# Filamint_Schematic_V4_3.net
KiCad netlist of a schematic drawn in EAGLE
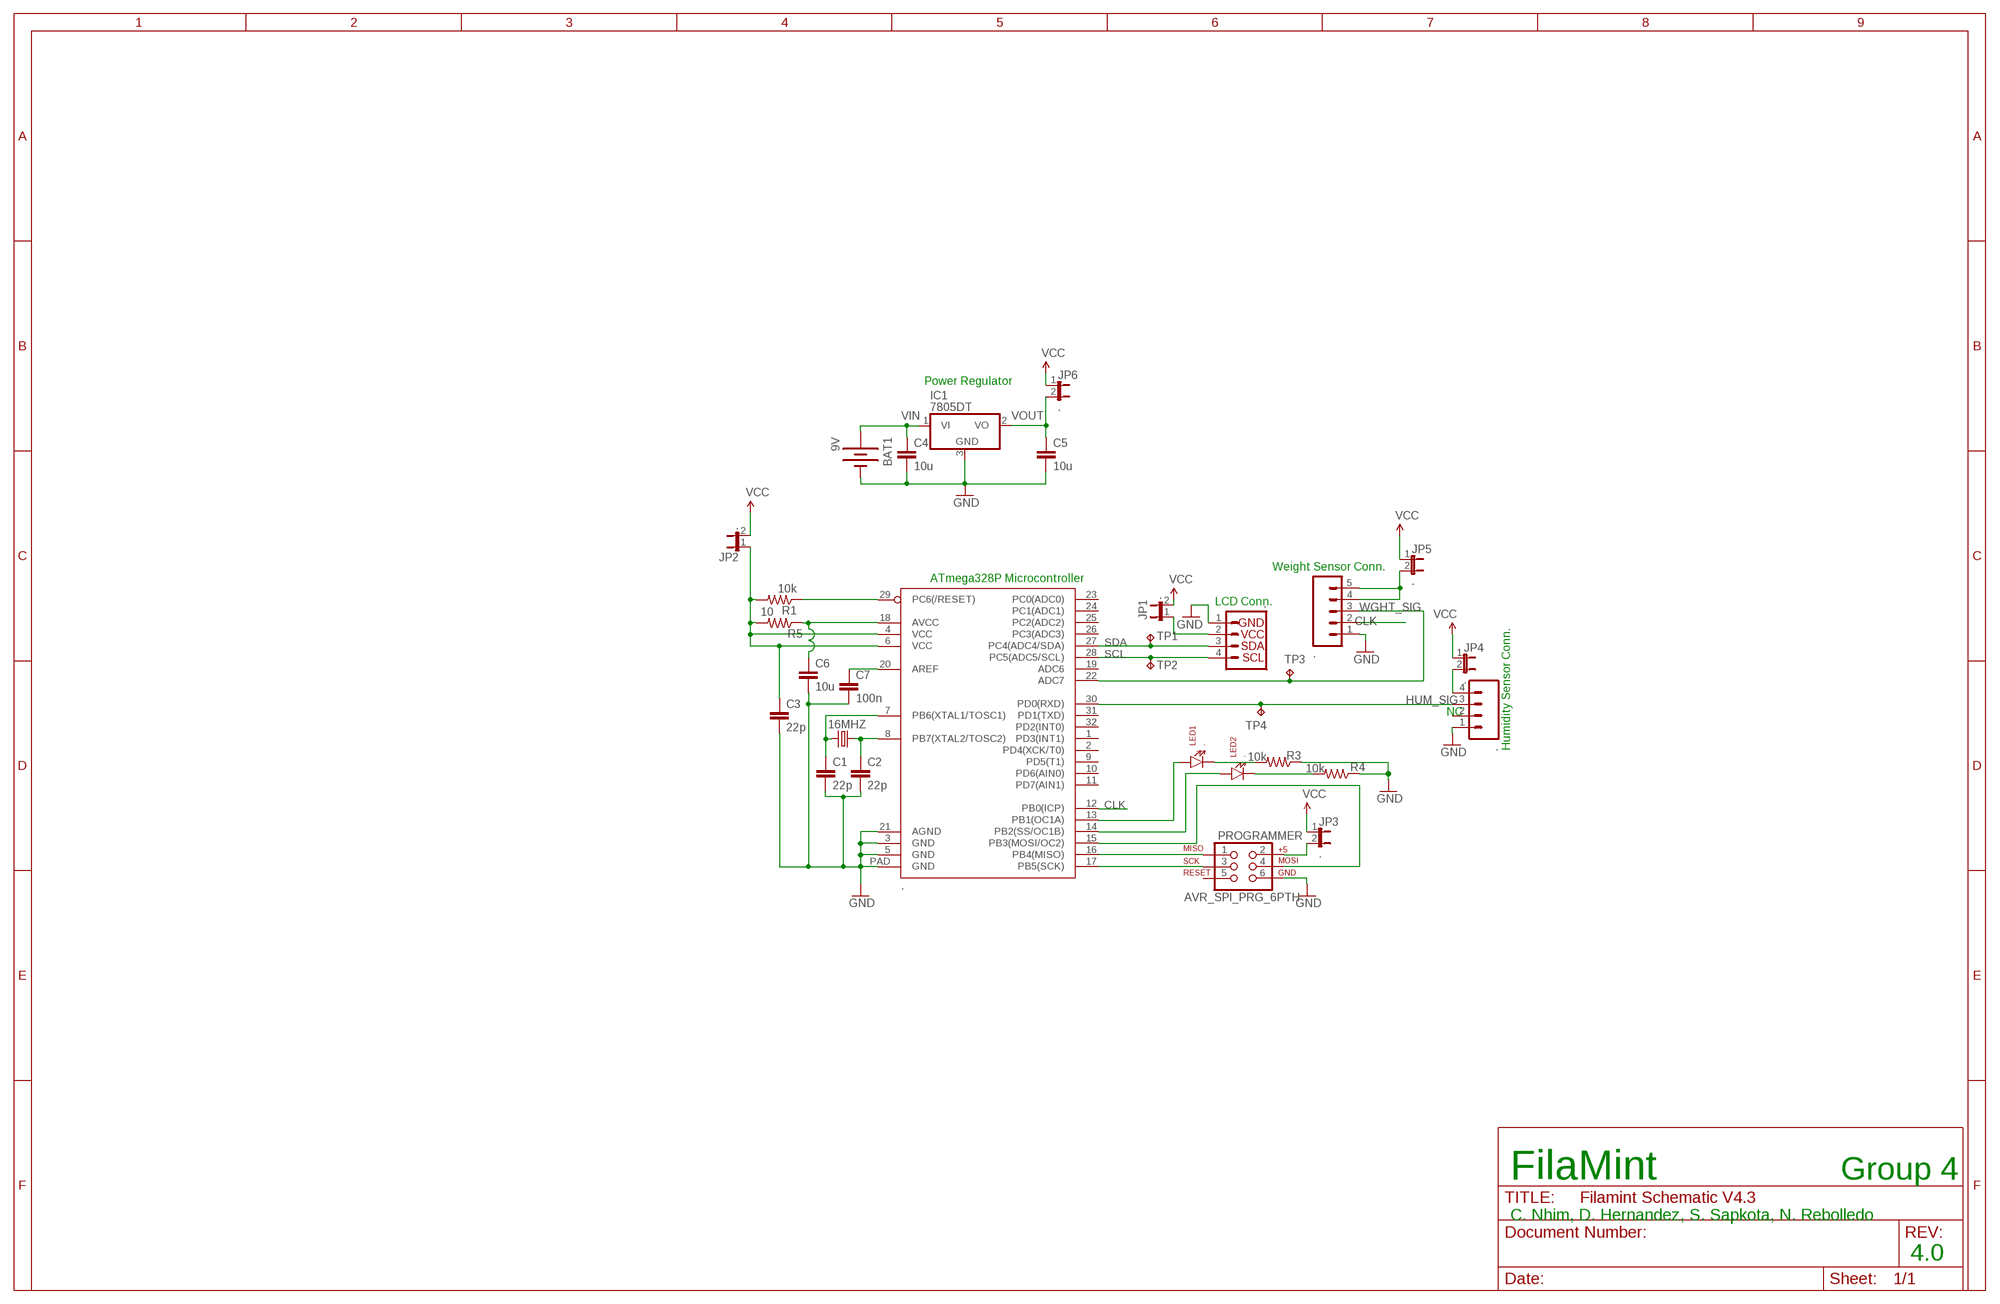
[diagram p0: schematic, sheet 1]

(export (version "E")
  (design (tool "Eeschema 10.0.6"))
  (components
    (comp (ref "16MHZ")
      (value "CSM-7X-DU")
      (footprint "eagle-import:CSM-7X-DU")
      (libsource (lib "eagle-import") (part "CSM-7X-DU"))
    )
    (comp (ref "BAT1")
      (value "9V")
      (footprint "eagle-import:BATTCON_9V")
      (libsource (lib "eagle-import") (part "BATTERY9V"))
    )
    (comp (ref "C1")
      (value "22p")
      (footprint "eagle-import:C025-024X044")
      (libsource (lib "eagle-import") (part "C-EU025-024X044"))
    )
    (comp (ref "C2")
      (value "22p")
      (footprint "eagle-import:C025-024X044")
      (libsource (lib "eagle-import") (part "C-EU025-024X044"))
    )
    (comp (ref "C3")
      (value "22p")
      (footprint "eagle-import:C025-024X044")
      (libsource (lib "eagle-import") (part "C-EU025-024X044"))
    )
    (comp (ref "C4")
      (value "10u")
      (footprint "eagle-import:C025-024X044")
      (libsource (lib "eagle-import") (part "C-EU025-024X044"))
    )
    (comp (ref "C5")
      (value "10u")
      (footprint "eagle-import:C025-024X044")
      (libsource (lib "eagle-import") (part "C-EU025-024X044"))
    )
    (comp (ref "C6")
      (value "10u")
      (footprint "eagle-import:C025-024X044")
      (libsource (lib "eagle-import") (part "C-EU025-024X044"))
    )
    (comp (ref "C7")
      (value "100n")
      (footprint "eagle-import:C025-024X044")
      (libsource (lib "eagle-import") (part "C-EU025-024X044"))
    )
    (comp (ref "DHT22")
      (value ".")
      (footprint "eagle-import:1X04-1MM-RA")
      (libsource (lib "eagle-import") (part "M04SMD2"))
    )
    (comp (ref "HX711")
      (value ".")
      (footprint "eagle-import:1X05-1MM")
      (libsource (lib "eagle-import") (part "M05SMD"))
    )
    (comp (ref "IC1")
      (value "7805DT")
      (footprint "eagle-import:TO252")
      (libsource (lib "eagle-import") (part "78DT05"))
    )
    (comp (ref "JP1")
      (value ".")
      (footprint "eagle-import:JP1")
      (libsource (lib "eagle-import") (part "JP1E"))
    )
    (comp (ref "JP2")
      (value ".")
      (footprint "eagle-import:JP1")
      (libsource (lib "eagle-import") (part "JP1E"))
    )
    (comp (ref "JP3")
      (value ".")
      (footprint "eagle-import:JP1")
      (libsource (lib "eagle-import") (part "JP1E"))
    )
    (comp (ref "JP4")
      (value ".")
      (footprint "eagle-import:JP1")
      (libsource (lib "eagle-import") (part "JP1E"))
    )
    (comp (ref "JP5")
      (value ".")
      (footprint "eagle-import:JP1")
      (libsource (lib "eagle-import") (part "JP1E"))
    )
    (comp (ref "JP6")
      (value ".")
      (footprint "eagle-import:JP1")
      (libsource (lib "eagle-import") (part "JP1E"))
    )
    (comp (ref "LCD")
      (value ".")
      (footprint "eagle-import:1X04")
      (libsource (lib "eagle-import") (part "I2C_STANDARD"))
    )
    (comp (ref "LED1")
      (value ".")
      (footprint "eagle-import:LTE-302")
      (libsource (lib "eagle-import") (part "LTE-302"))
    )
    (comp (ref "LED2")
      (value ".")
      (footprint "eagle-import:LTE-302")
      (libsource (lib "eagle-import") (part "LTE-302"))
    )
    (comp (ref "MICROCONTROLLER")
      (value ".")
      (footprint "eagle-import:MLF32-PAD")
      (libsource (lib "eagle-import") (part "ATMEGA328P_MLFMLF32"))
    )
    (comp (ref "PROGRAMMER")
      (value "AVR_SPI_PRG_6PTH")
      (footprint "eagle-import:2X3")
      (libsource (lib "eagle-import") (part "AVR_SPI_PRG_6PTH"))
    )
    (comp (ref "R1")
      (value "10k")
      (footprint "eagle-import:0204_5")
      (libsource (lib "eagle-import") (part "R-US_0204/5"))
    )
    (comp (ref "R3")
      (value "10k")
      (footprint "eagle-import:0204_5")
      (libsource (lib "eagle-import") (part "R-US_0204/5"))
    )
    (comp (ref "R4")
      (value "10k")
      (footprint "eagle-import:0204_5")
      (libsource (lib "eagle-import") (part "R-US_0204/5"))
    )
    (comp (ref "R5")
      (value "10")
      (footprint "eagle-import:0204_5")
      (libsource (lib "eagle-import") (part "R-US_0204/5"))
    )
    (comp (ref "TP1")
      (value "TPB1,27")
      (footprint "eagle-import:B1,27")
      (libsource (lib "eagle-import") (part "TPB1,27"))
    )
    (comp (ref "TP2")
      (value "TPB1,27")
      (footprint "eagle-import:B1,27")
      (libsource (lib "eagle-import") (part "TPB1,27"))
    )
    (comp (ref "TP3")
      (value "TPB1,27")
      (footprint "eagle-import:B1,27")
      (libsource (lib "eagle-import") (part "TPB1,27"))
    )
    (comp (ref "TP4")
      (value "TPB1,27")
      (footprint "eagle-import:B1,27")
      (libsource (lib "eagle-import") (part "TPB1,27"))
    )
  )
  (nets
    (net (code "1") (name "/CLK") (class "Default")
      (node (ref "HX711") (pin "2") (pinfunction "2_2") (pintype "passive"))
      (node (ref "MICROCONTROLLER") (pin "12") (pinfunction "PB0(ICP)_12") (pintype "bidirectional"))
    )
    (net (code "2") (name "/HUM_SIG") (class "Default")
      (node (ref "DHT22") (pin "3") (pinfunction "3_3") (pintype "passive"))
      (node (ref "MICROCONTROLLER") (pin "30") (pinfunction "PD0(RXD)_30") (pintype "bidirectional"))
      (node (ref "TP4") (pin "TP") (pinfunction "TP_TP") (pintype "input"))
    )
    (net (code "3") (name "/SCL") (class "Default")
      (node (ref "LCD") (pin "4") (pinfunction "4_4") (pintype "passive"))
      (node (ref "MICROCONTROLLER") (pin "28") (pinfunction "PC5(ADC5/SCL)_28") (pintype "bidirectional"))
      (node (ref "TP2") (pin "TP") (pinfunction "TP_TP") (pintype "input"))
    )
    (net (code "4") (name "/SDA") (class "Default")
      (node (ref "LCD") (pin "3") (pinfunction "3_3") (pintype "passive"))
      (node (ref "MICROCONTROLLER") (pin "27") (pinfunction "PC4(ADC4/SDA)_27") (pintype "bidirectional"))
      (node (ref "TP1") (pin "TP") (pinfunction "TP_TP") (pintype "input"))
    )
    (net (code "5") (name "/VIN") (class "Default")
      (node (ref "BAT1") (pin "+") (pinfunction "+_+") (pintype "power_in"))
      (node (ref "C4") (pin "1") (pinfunction "1_1") (pintype "passive"))
      (node (ref "IC1") (pin "1") (pinfunction "VI_1") (pintype "input"))
    )
    (net (code "6") (name "/WGHT_SIG") (class "Default")
      (node (ref "HX711") (pin "3") (pinfunction "3_3") (pintype "passive"))
      (node (ref "MICROCONTROLLER") (pin "22") (pinfunction "ADC7_22") (pintype "bidirectional"))
      (node (ref "TP3") (pin "TP") (pinfunction "TP_TP") (pintype "input"))
    )
    (net (code "7") (name "GND") (class "Default")
      (node (ref "BAT1") (pin "-") (pinfunction "-_-") (pintype "power_in"))
      (node (ref "C1") (pin "2") (pinfunction "2_2") (pintype "passive"))
      (node (ref "C2") (pin "2") (pinfunction "2_2") (pintype "passive"))
      (node (ref "C3") (pin "2") (pinfunction "2_2") (pintype "passive"))
      (node (ref "C4") (pin "2") (pinfunction "2_2") (pintype "passive"))
      (node (ref "C5") (pin "2") (pinfunction "2_2") (pintype "passive"))
      (node (ref "C6") (pin "2") (pinfunction "2_2") (pintype "passive"))
      (node (ref "C7") (pin "2") (pinfunction "2_2") (pintype "passive"))
      (node (ref "DHT22") (pin "1") (pinfunction "1_1") (pintype "passive"))
      (node (ref "HX711") (pin "1") (pinfunction "1_1") (pintype "passive"))
      (node (ref "IC1") (pin "3") (pinfunction "GND_3") (pintype "passive"))
      (node (ref "LCD") (pin "1") (pinfunction "1_1") (pintype "passive"))
      (node (ref "MICROCONTROLLER") (pin "21") (pinfunction "AGND_21") (pintype "bidirectional"))
      (node (ref "MICROCONTROLLER") (pin "3") (pinfunction "GND_3") (pintype "bidirectional"))
      (node (ref "MICROCONTROLLER") (pin "5") (pinfunction "GND_5") (pintype "bidirectional"))
      (node (ref "MICROCONTROLLER") (pin "PAD") (pinfunction "GND_PAD") (pintype "bidirectional"))
      (node (ref "PROGRAMMER") (pin "6") (pinfunction "6_6") (pintype "passive"))
      (node (ref "R3") (pin "1") (pinfunction "1_1") (pintype "passive"))
      (node (ref "R4") (pin "1") (pinfunction "1_1") (pintype "passive"))
    )
    (net (code "8") (name "Net-(C3-Pad1)") (class "Default")
      (node (ref "C3") (pin "1") (pinfunction "1_1") (pintype "passive"))
      (node (ref "JP2") (pin "1") (pinfunction "1_1") (pintype "passive"))
      (node (ref "MICROCONTROLLER") (pin "4") (pinfunction "VCC_4") (pintype "bidirectional"))
      (node (ref "MICROCONTROLLER") (pin "6") (pinfunction "VCC_6") (pintype "bidirectional"))
      (node (ref "R1") (pin "2") (pinfunction "2_2") (pintype "passive"))
      (node (ref "R5") (pin "2") (pinfunction "2_2") (pintype "passive"))
    )
    (net (code "9") (name "Net-(DHT22-Pad4)") (class "Default")
      (node (ref "DHT22") (pin "4") (pinfunction "4_4") (pintype "passive"))
      (node (ref "JP4") (pin "2") (pinfunction "2_2") (pintype "passive"))
    )
    (net (code "10") (name "Net-(HX711-Pad4)") (class "Default")
      (node (ref "HX711") (pin "4") (pinfunction "4_4") (pintype "passive"))
      (node (ref "HX711") (pin "5") (pinfunction "5_5") (pintype "passive"))
      (node (ref "JP5") (pin "2") (pinfunction "2_2") (pintype "passive"))
    )
    (net (code "11") (name "Net-(IC1-VO)") (class "Default")
      (node (ref "C5") (pin "1") (pinfunction "1_1") (pintype "passive"))
      (node (ref "IC1") (pin "2") (pinfunction "VO_2") (pintype "passive"))
      (node (ref "JP6") (pin "2") (pinfunction "2_2") (pintype "passive"))
    )
    (net (code "12") (name "Net-(JP1-Pad1)") (class "Default")
      (node (ref "JP1") (pin "1") (pinfunction "1_1") (pintype "passive"))
      (node (ref "LCD") (pin "2") (pinfunction "2_2") (pintype "passive"))
    )
    (net (code "13") (name "Net-(JP3-Pad2)") (class "Default")
      (node (ref "JP3") (pin "2") (pinfunction "2_2") (pintype "passive"))
      (node (ref "PROGRAMMER") (pin "2") (pinfunction "2_2") (pintype "passive"))
    )
    (net (code "14") (name "Net-(LED1-PadC)") (class "Default")
      (node (ref "LED1") (pin "C") (pinfunction "C_C") (pintype "bidirectional"))
      (node (ref "R3") (pin "2") (pinfunction "2_2") (pintype "passive"))
    )
    (net (code "15") (name "Net-(LED2-PadC)") (class "Default")
      (node (ref "LED2") (pin "C") (pinfunction "C_C") (pintype "bidirectional"))
      (node (ref "R4") (pin "2") (pinfunction "2_2") (pintype "passive"))
    )
    (net (code "16") (name "Net-(MICROCONTROLLER-AREF)") (class "Default")
      (node (ref "C7") (pin "1") (pinfunction "1_1") (pintype "passive"))
      (node (ref "MICROCONTROLLER") (pin "20") (pinfunction "AREF_20") (pintype "bidirectional"))
    )
    (net (code "17") (name "Net-(MICROCONTROLLER-AVCC)") (class "Default")
      (node (ref "C6") (pin "1") (pinfunction "1_1") (pintype "passive"))
      (node (ref "MICROCONTROLLER") (pin "18") (pinfunction "AVCC_18") (pintype "bidirectional"))
      (node (ref "R5") (pin "1") (pinfunction "1_1") (pintype "passive"))
    )
    (net (code "18") (name "Net-(MICROCONTROLLER-PB1(OC1A))") (class "Default")
      (node (ref "LED1") (pin "A") (pinfunction "A_A") (pintype "bidirectional"))
      (node (ref "MICROCONTROLLER") (pin "13") (pinfunction "PB1(OC1A)_13") (pintype "bidirectional"))
    )
    (net (code "19") (name "Net-(MICROCONTROLLER-PB2(SS{slash}OC1B))") (class "Default")
      (node (ref "LED2") (pin "A") (pinfunction "A_A") (pintype "bidirectional"))
      (node (ref "MICROCONTROLLER") (pin "14") (pinfunction "PB2(SS/OC1B)_14") (pintype "bidirectional"))
    )
    (net (code "20") (name "Net-(MICROCONTROLLER-PB3(MOSI{slash}OC2))") (class "Default")
      (node (ref "MICROCONTROLLER") (pin "15") (pinfunction "PB3(MOSI/OC2)_15") (pintype "bidirectional"))
      (node (ref "PROGRAMMER") (pin "4") (pinfunction "4_4") (pintype "passive"))
    )
    (net (code "21") (name "Net-(MICROCONTROLLER-PB4(MISO))") (class "Default")
      (node (ref "MICROCONTROLLER") (pin "16") (pinfunction "PB4(MISO)_16") (pintype "bidirectional"))
      (node (ref "PROGRAMMER") (pin "1") (pinfunction "1_1") (pintype "passive"))
    )
    (net (code "22") (name "Net-(MICROCONTROLLER-PB5(SCK))") (class "Default")
      (node (ref "MICROCONTROLLER") (pin "17") (pinfunction "PB5(SCK)_17") (pintype "bidirectional"))
      (node (ref "PROGRAMMER") (pin "3") (pinfunction "3_3") (pintype "passive"))
    )
    (net (code "23") (name "Net-(MICROCONTROLLER-PB6(XTAL1{slash}TOSC1))") (class "Default")
      (node (ref "16MHZ") (pin "2") (pinfunction "2_2") (pintype "passive"))
      (node (ref "C1") (pin "1") (pinfunction "1_1") (pintype "passive"))
      (node (ref "MICROCONTROLLER") (pin "7") (pinfunction "PB6(XTAL1/TOSC1)_7") (pintype "bidirectional"))
    )
    (net (code "24") (name "Net-(MICROCONTROLLER-PB7(XTAL2{slash}TOSC2))") (class "Default")
      (node (ref "16MHZ") (pin "1") (pinfunction "1_1") (pintype "passive"))
      (node (ref "C2") (pin "1") (pinfunction "1_1") (pintype "passive"))
      (node (ref "MICROCONTROLLER") (pin "8") (pinfunction "PB7(XTAL2/TOSC2)_8") (pintype "bidirectional"))
    )
    (net (code "25") (name "Net-(MICROCONTROLLER-PC6({slash}RESET))") (class "Default")
      (node (ref "MICROCONTROLLER") (pin "29") (pinfunction "PC6(/RESET)_29") (pintype "bidirectional"))
      (node (ref "R1") (pin "1") (pinfunction "1_1") (pintype "passive"))
    )
    (net (code "26") (name "VCC") (class "Default")
      (node (ref "JP1") (pin "2") (pinfunction "2_2") (pintype "passive"))
      (node (ref "JP2") (pin "2") (pinfunction "2_2") (pintype "passive"))
      (node (ref "JP3") (pin "1") (pinfunction "1_1") (pintype "passive"))
      (node (ref "JP4") (pin "1") (pinfunction "1_1") (pintype "passive"))
      (node (ref "JP5") (pin "1") (pinfunction "1_1") (pintype "passive"))
      (node (ref "JP6") (pin "1") (pinfunction "1_1") (pintype "passive"))
    )
    (net (code "27") (name "unconnected-(DHT22-Pad2)") (class "Default")
      (node (ref "DHT22") (pin "2") (pinfunction "2_2") (pintype "passive"))
    )
    (net (code "28") (name "unconnected-(MICROCONTROLLER-ADC6-Pad19)") (class "Default")
      (node (ref "MICROCONTROLLER") (pin "19") (pinfunction "ADC6_19") (pintype "bidirectional"))
    )
    (net (code "29") (name "unconnected-(MICROCONTROLLER-PC0(ADC0)-Pad23)") (class "Default")
      (node (ref "MICROCONTROLLER") (pin "23") (pinfunction "PC0(ADC0)_23") (pintype "bidirectional"))
    )
    (net (code "30") (name "unconnected-(MICROCONTROLLER-PC1(ADC1)-Pad24)") (class "Default")
      (node (ref "MICROCONTROLLER") (pin "24") (pinfunction "PC1(ADC1)_24") (pintype "bidirectional"))
    )
    (net (code "31") (name "unconnected-(MICROCONTROLLER-PC2(ADC2)-Pad25)") (class "Default")
      (node (ref "MICROCONTROLLER") (pin "25") (pinfunction "PC2(ADC2)_25") (pintype "bidirectional"))
    )
    (net (code "32") (name "unconnected-(MICROCONTROLLER-PC3(ADC3)-Pad26)") (class "Default")
      (node (ref "MICROCONTROLLER") (pin "26") (pinfunction "PC3(ADC3)_26") (pintype "bidirectional"))
    )
    (net (code "33") (name "unconnected-(MICROCONTROLLER-PD1(TXD)-Pad31)") (class "Default")
      (node (ref "MICROCONTROLLER") (pin "31") (pinfunction "PD1(TXD)_31") (pintype "bidirectional"))
    )
    (net (code "34") (name "unconnected-(MICROCONTROLLER-PD2(INT0)-Pad32)") (class "Default")
      (node (ref "MICROCONTROLLER") (pin "32") (pinfunction "PD2(INT0)_32") (pintype "bidirectional"))
    )
    (net (code "35") (name "unconnected-(MICROCONTROLLER-PD3(INT1)-Pad1)") (class "Default")
      (node (ref "MICROCONTROLLER") (pin "1") (pinfunction "PD3(INT1)_1") (pintype "bidirectional"))
    )
    (net (code "36") (name "unconnected-(MICROCONTROLLER-PD4(XCK{slash}T0)-Pad2)") (class "Default")
      (node (ref "MICROCONTROLLER") (pin "2") (pinfunction "PD4(XCK/T0)_2") (pintype "bidirectional"))
    )
    (net (code "37") (name "unconnected-(MICROCONTROLLER-PD5(T1)-Pad9)") (class "Default")
      (node (ref "MICROCONTROLLER") (pin "9") (pinfunction "PD5(T1)_9") (pintype "bidirectional"))
    )
    (net (code "38") (name "unconnected-(MICROCONTROLLER-PD6(AIN0)-Pad10)") (class "Default")
      (node (ref "MICROCONTROLLER") (pin "10") (pinfunction "PD6(AIN0)_10") (pintype "bidirectional"))
    )
    (net (code "39") (name "unconnected-(MICROCONTROLLER-PD7(AIN1)-Pad11)") (class "Default")
      (node (ref "MICROCONTROLLER") (pin "11") (pinfunction "PD7(AIN1)_11") (pintype "bidirectional"))
    )
    (net (code "40") (name "unconnected-(PROGRAMMER-Pad5)") (class "Default")
      (node (ref "PROGRAMMER") (pin "5") (pinfunction "5_5") (pintype "passive"))
    )
  )
)
